# CPU.net
KiCad netlist of a schematic drawn in Altium Designer
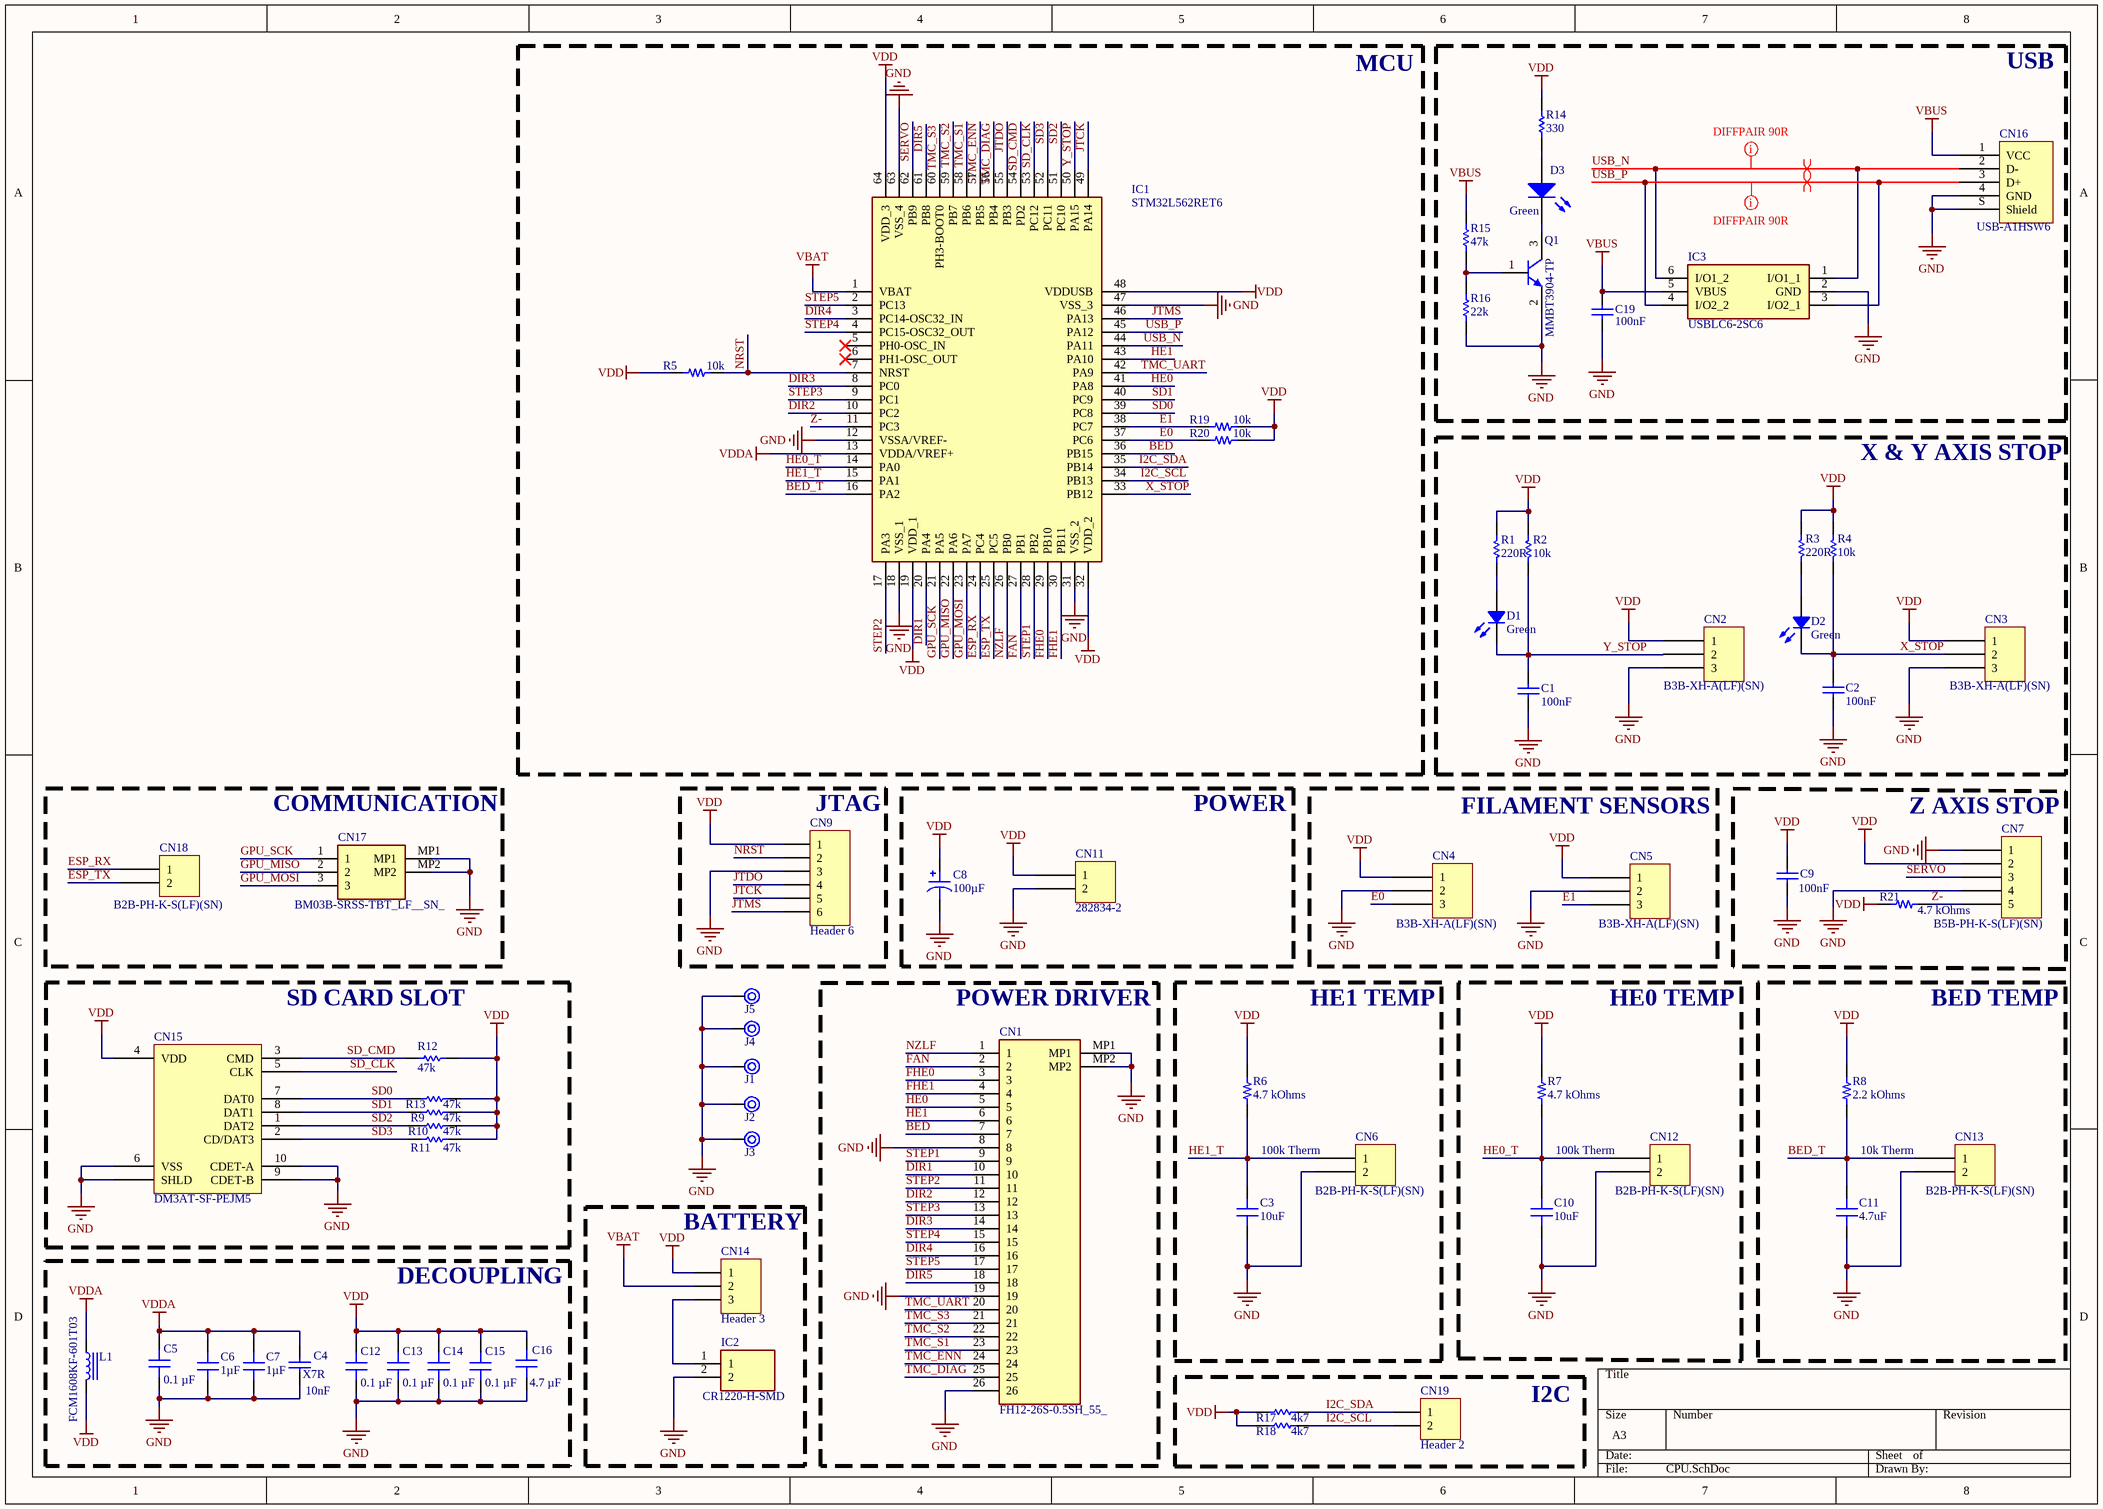
[diagram p0: CPU.SchDoc]

(export (version "E")
  (design (tool "Eeschema 10.0.6"))
  (components
    (comp (ref "C1")
      (value "100nF")
      (footprint "1608[0603]")
      (description "Capacitor")
      (fields (field (name "Comment") "X5R") (field (name "PUBLISHER") "Altium Limited"))
      (libsource (lib "Miscellaneous Devices") (part "Cap"))
    )
    (comp (ref "C2")
      (value "100nF")
      (footprint "1608[0603]")
      (description "Capacitor")
      (fields (field (name "Comment") "X5R") (field (name "PUBLISHER") "Altium Limited"))
      (libsource (lib "Miscellaneous Devices") (part "Cap"))
    )
    (comp (ref "C3")
      (value "10uF")
      (footprint "CAP 0603_1608")
      (description "CAP CER 1UF 16V X5R 0603")
      (fields (field (name "PART NUMBER") "0603YD105KAT4A") (field (name "MANUFACTURER") "AVX Corporation"))
      (libsource (lib "Celestial Altium Library - altium_library") (part "Capacitor"))
    )
    (comp (ref "C4")
      (value "X7R")
      (footprint "1608[0603]")
      (description "Capacitor")
      (fields (field (name "ALTIUM_VALUE") "10nF") (field (name "PUBLISHER") "Altium Limited"))
      (libsource (lib "Miscellaneous Devices") (part "Cap"))
    )
    (comp (ref "C5")
      (value "0.1 µF")
      (footprint "CAP 0603_1608")
      (description "CAP CER 0.1UF 100V X7R 0603")
      (fields
        (field (name "PART NUMBER") "0603B104K101CT")
        (field (name "MANUFACTURER") "Walsin Technology Corporation")
      )
      (libsource (lib "Celestial Altium Library - altium_library") (part "Capacitor"))
    )
    (comp (ref "C6")
      (value "1µF")
      (footprint "CAP 0603_1608")
      (description "CAP CER 1UF 16V X5R 0603")
      (fields (field (name "PART NUMBER") "0603YD105KAT4A") (field (name "MANUFACTURER") "AVX Corporation"))
      (libsource (lib "Celestial Altium Library - altium_library") (part "Capacitor"))
    )
    (comp (ref "C7")
      (value "1µF")
      (footprint "CAP 0603_1608")
      (description "CAP CER 1UF 16V X5R 0603")
      (fields (field (name "PART NUMBER") "0603YD105KAT4A") (field (name "MANUFACTURER") "AVX Corporation"))
      (libsource (lib "Celestial Altium Library - altium_library") (part "Capacitor"))
    )
    (comp (ref "C8")
      (value "100µF")
      (footprint "CAP ALSMD POLY 5.3MM H6.0MM")
      (description "CAP ALUM POLY 100UF 20% 6.3V SMD")
      (fields
        (field (name "PART NUMBER") "6SVPC100M")
        (field (name "MANUFACTURER") "Panasonic Electronic Components")
      )
      (libsource (lib "Celestial Altium Library - altium_library") (part "Polarised Capacitor"))
    )
    (comp (ref "C9")
      (value "100nF")
      (footprint "1608[0603]")
      (description "Capacitor")
      (fields (field (name "Comment") "X5R") (field (name "PUBLISHER") "Altium Limited"))
      (libsource (lib "Miscellaneous Devices") (part "Cap"))
    )
    (comp (ref "C10")
      (value "10uF")
      (footprint "CAP 0603_1608")
      (description "CAP CER 1UF 16V X5R 0603")
      (fields (field (name "PART NUMBER") "0603YD105KAT4A") (field (name "MANUFACTURER") "AVX Corporation"))
      (libsource (lib "Celestial Altium Library - altium_library") (part "Capacitor"))
    )
    (comp (ref "C11")
      (value "4.7uF")
      (footprint "CAP 0603_1608")
      (description "CAP CER 1UF 16V X5R 0603")
      (fields (field (name "PART NUMBER") "0603YD105KAT4A") (field (name "MANUFACTURER") "AVX Corporation"))
      (libsource (lib "Celestial Altium Library - altium_library") (part "Capacitor"))
    )
    (comp (ref "C12")
      (value "0.1 µF")
      (footprint "CAP 0603_1608")
      (description "CAP CER 0.1UF 100V X7R 0603")
      (fields
        (field (name "PART NUMBER") "0603B104K101CT")
        (field (name "MANUFACTURER") "Walsin Technology Corporation")
      )
      (libsource (lib "Celestial Altium Library - altium_library") (part "Capacitor"))
    )
    (comp (ref "C13")
      (value "0.1 µF")
      (footprint "CAP 0603_1608")
      (description "CAP CER 0.1UF 100V X7R 0603")
      (fields
        (field (name "PART NUMBER") "0603B104K101CT")
        (field (name "MANUFACTURER") "Walsin Technology Corporation")
      )
      (libsource (lib "Celestial Altium Library - altium_library") (part "Capacitor"))
    )
    (comp (ref "C14")
      (value "0.1 µF")
      (footprint "CAP 0603_1608")
      (description "CAP CER 0.1UF 100V X7R 0603")
      (fields
        (field (name "PART NUMBER") "0603B104K101CT")
        (field (name "MANUFACTURER") "Walsin Technology Corporation")
      )
      (libsource (lib "Celestial Altium Library - altium_library") (part "Capacitor"))
    )
    (comp (ref "C15")
      (value "0.1 µF")
      (footprint "CAP 0603_1608")
      (description "CAP CER 0.1UF 100V X7R 0603")
      (fields
        (field (name "PART NUMBER") "0603B104K101CT")
        (field (name "MANUFACTURER") "Walsin Technology Corporation")
      )
      (libsource (lib "Celestial Altium Library - altium_library") (part "Capacitor"))
    )
    (comp (ref "C16")
      (value "4.7 µF")
      (footprint "CAP 0603_1608")
      (description "CAP CER 4.7UF 16V X5R 0603")
      (fields
        (field (name "PART NUMBER") "GRM185R61C475KE11D")
        (field (name "MANUFACTURER") "Murata Electronics")
      )
      (libsource (lib "Celestial Altium Library - altium_library") (part "Capacitor"))
    )
    (comp (ref "C19")
      (value "100nF")
      (footprint "1608[0603]")
      (description "Capacitor")
      (fields (field (name "Comment") "Cap") (field (name "PUBLISHER") "Altium Limited"))
      (libsource (lib "Miscellaneous Devices") (part "Cap"))
    )
    (comp (ref "CN1")
      (value "FH12-26S-0.5SH_55_")
      (footprint "SamacSys:FH1226S05SH55")
      (description "Connector")
      (fields
        (field (name "MANUFACTURER_PART_NUMBER") "FH12-26S-0.5SH(55)")
        (field (name "MOUSER PART NUMBER") "798-FH12-26S-0.5SH55")
      )
      (libsource (lib "SamacSys") (part "FH12-26S-0.5SH_55_"))
    )
    (comp (ref "CN2")
      (value "B3B-XH-A(LF)(SN)")
      (footprint "JST XH B3B-XH-A")
      (description "CONN HEADER VERT 3POS 2.5MM")
      (fields (field (name "MANUFACTURER") "JST Sales America Inc."))
      (libsource (lib "Celestial Altium Library - altium_library") (part "3 Pin"))
    )
    (comp (ref "CN3")
      (value "B3B-XH-A(LF)(SN)")
      (footprint "JST XH B3B-XH-A")
      (description "CONN HEADER VERT 3POS 2.5MM")
      (fields (field (name "MANUFACTURER") "JST Sales America Inc."))
      (libsource (lib "Celestial Altium Library - altium_library") (part "3 Pin"))
    )
    (comp (ref "CN4")
      (value "B3B-XH-A(LF)(SN)")
      (footprint "JST XH B3B-XH-A")
      (description "CONN HEADER VERT 3POS 2.5MM")
      (fields (field (name "MANUFACTURER") "JST Sales America Inc."))
      (libsource (lib "Celestial Altium Library - altium_library") (part "3 Pin"))
    )
    (comp (ref "CN5")
      (value "B3B-XH-A(LF)(SN)")
      (footprint "JST XH B3B-XH-A")
      (description "CONN HEADER VERT 3POS 2.5MM")
      (fields (field (name "MANUFACTURER") "JST Sales America Inc."))
      (libsource (lib "Celestial Altium Library - altium_library") (part "3 Pin"))
    )
    (comp (ref "CN6")
      (value "B2B-PH-K-S(LF)(SN)")
      (footprint "JST B2B-PH-K")
      (description "CONN HEADER VERT 2POS 2MM")
      (fields (field (name "MANUFACTURER") "JST Sales America Inc."))
      (libsource (lib "Celestial Altium Library - altium_library") (part "2 Pin"))
    )
    (comp (ref "CN7")
      (value "B5B-PH-K-S(LF)(SN)")
      (footprint "JST B5B-PH-K")
      (description "CONN HEADER VERT 5POS 2MM")
      (fields (field (name "MANUFACTURER") "JST Sales America Inc."))
      (libsource (lib "Celestial Altium Library - altium_library") (part "5 Pin"))
    )
    (comp (ref "CN9")
      (value "Header 6")
      (footprint "HDR1X6")
      (description "Header, 6-Pin")
      (fields (field (name "PUBLISHER") "Altium Limited"))
      (libsource (lib "Miscellaneous Connectors") (part "Header 6"))
    )
    (comp (ref "CN11")
      (value "282834-2")
      (footprint "TE 282834-2")
      (description "TERM BLK 2P SIDE ENT 2.54MM PCB")
      (fields (field (name "MANUFACTURER") "TE Connectivity AMP Connectors") (field (name "VOLTAGE") "150V"))
      (libsource (lib "Celestial Altium Library - altium_library") (part "2 Pin"))
    )
    (comp (ref "CN12")
      (value "B2B-PH-K-S(LF)(SN)")
      (footprint "JST B2B-PH-K")
      (description "CONN HEADER VERT 2POS 2MM")
      (fields (field (name "MANUFACTURER") "JST Sales America Inc."))
      (libsource (lib "Celestial Altium Library - altium_library") (part "2 Pin"))
    )
    (comp (ref "CN13")
      (value "B2B-PH-K-S(LF)(SN)")
      (footprint "JST B2B-PH-K")
      (description "CONN HEADER VERT 2POS 2MM")
      (fields (field (name "MANUFACTURER") "JST Sales America Inc."))
      (libsource (lib "Celestial Altium Library - altium_library") (part "2 Pin"))
    )
    (comp (ref "CN14")
      (value "Header 3")
      (footprint "HDR1X3")
      (description "Header, 3-Pin")
      (fields (field (name "PUBLISHER") "Altium Limited"))
      (libsource (lib "Miscellaneous Connectors") (part "Header 3"))
    )
    (comp (ref "CN15")
      (value "DM3AT-SF-PEJM5")
      (footprint "HIROSE DM3AT-SF-PEJM5")
      (description "CONN MICRO SD CARD PUSH-PUSH R/A")
      (fields (field (name "MANUFACTURER") "Hirose Electric Co Ltd"))
      (libsource (lib "Celestial Altium Library - altium_library") (part "Hirose DM3 MicroSD"))
    )
    (comp (ref "CN16")
      (value "USB-A1HSW6")
      (footprint "ON SHORE TECHNOLOGY USB-A1HSW6")
      (description "CONN RCPT TYPEA 4POS R/A")
      (fields (field (name "MANUFACTURER") "On Shore Technology Inc."))
      (libsource (lib "Celestial Altium Library - altium_library") (part "USB 2.0 TYPE A"))
    )
    (comp (ref "CN17")
      (value "BM03B-SRSS-TBT_LF__SN_")
      (footprint "SamacSys:BM03BSRSSTBTLFSN")
      (description "Connector")
      (fields (field (name "MANUFACTURER_PART_NUMBER") "BM03B-SRSS-TBT(LF)(SN)"))
      (libsource (lib "*") (part "BM03B-SRSS-TBT_LF__SN_"))
    )
    (comp (ref "CN18")
      (value "B2B-PH-K-S(LF)(SN)")
      (footprint "JST B2B-PH-K")
      (description "CONN HEADER VERT 2POS 2MM")
      (fields (field (name "MANUFACTURER") "JST Sales America Inc."))
      (libsource (lib "Celestial Altium Library - altium_library") (part "2 Pin"))
    )
    (comp (ref "CN19")
      (value "Header 2")
      (footprint "HDR1X2")
      (description "Header, 2-Pin")
      (fields (field (name "PUBLISHER") "Altium Limited"))
      (libsource (lib "Miscellaneous Connectors") (part "Header 2"))
    )
    (comp (ref "D1")
      (value "Green")
      (footprint "LED 0805_2012 GREEN")
      (description "LED GREEN CLEAR 0805 SMD")
      (fields
        (field (name "PART NUMBER") "QTLP630C4TR")
        (field (name "MANUFACTURER") "Everlight Electronics Co Ltd")
      )
      (libsource (lib "Celestial Altium Library - altium_library") (part "LED"))
    )
    (comp (ref "D2")
      (value "Green")
      (footprint "LED 0805_2012 GREEN")
      (description "LED GREEN CLEAR 0805 SMD")
      (fields
        (field (name "PART NUMBER") "QTLP630C4TR")
        (field (name "MANUFACTURER") "Everlight Electronics Co Ltd")
      )
      (libsource (lib "Celestial Altium Library - altium_library") (part "LED"))
    )
    (comp (ref "D3")
      (value "Green")
      (footprint "1608[0603]")
      (description "Typical BLUE SiC LED")
      (fields (field (name "PUBLISHER") "Altium Limited"))
      (libsource (lib "Miscellaneous Devices") (part "LED3"))
    )
    (comp (ref "IC1")
      (value "STM32L562RET6")
      (footprint "SamacSys:QFP50P1200X1200X160-64N")
      (description "Integrated Circuit")
      (fields (field (name "MOUSER PART NUMBER") "511-STM32L562RET6"))
      (libsource (lib "*") (part "STM32L562RET6"))
    )
    (comp (ref "IC2")
      (value "CR1220-H-SMD")
      (footprint "SamacSys:CR1220HSMD")
      (description "Integrated Circuit")
      (libsource (lib "*") (part "CR1220-H-SMD"))
    )
    (comp (ref "IC3")
      (value "USBLC6-2SC6")
      (footprint "SamacSys:SOT95P280X145-6N")
      (description "Integrated Circuit")
      (fields (field (name "MOUSER PART NUMBER") "511-USBLC6-2SC6"))
      (libsource (lib "*") (part "USBLC6-2SC6"))
    )
    (comp (ref "J1")
      (value "PTH 3.2mm")
      (footprint "PTH 3.2mm")
      (libsource (lib "Integrated_Library1") (part "PTH 3.2mm"))
    )
    (comp (ref "J2")
      (value "PTH 3.2mm")
      (footprint "PTH 3.2mm")
      (libsource (lib "Integrated_Library1") (part "PTH 3.2mm"))
    )
    (comp (ref "J3")
      (value "PTH 3.2mm")
      (footprint "PTH 3.2mm")
      (libsource (lib "Integrated_Library1") (part "PTH 3.2mm"))
    )
    (comp (ref "J4")
      (value "PTH 3.2mm")
      (footprint "PTH 3.2mm")
      (libsource (lib "Integrated_Library1") (part "PTH 3.2mm"))
    )
    (comp (ref "J5")
      (value "PTH 3.2mm")
      (footprint "PTH 3.2mm")
      (libsource (lib "Integrated_Library1") (part "PTH 3.2mm"))
    )
    (comp (ref "L1")
      (value "FCM1608KF-601T03")
      (footprint "IND 0603_1608 RF WW")
      (description "FIXED IND 27NH 780MA 200 MOHM")
      (fields (field (name "PART NUMBER") "744917127") (field (name "MANUFACTURER") "Würth Elektronik"))
      (libsource (lib "Celestial Altium Library - altium_library") (part "Inductor"))
    )
    (comp (ref "Q1")
      (value "MMBT3904-TP")
      (footprint "MCCSEMI SOT-23-3")
      (description "TRANS NPN 40V 0.2A SOT23")
      (fields (field (name "MANUFACTURER") "Micro Commercial Co"))
      (libsource (lib "Celestial Altium Library - altium_library") (part "MCCSEMI NPN SOT-23-3"))
    )
    (comp (ref "R1")
      (value "220R")
      (footprint "1608[0603]")
      (description "Resistor")
      (fields (field (name "Comment") "Res1") (field (name "PUBLISHER") "Altium Limited"))
      (libsource (lib "Miscellaneous Devices") (part "Res1"))
    )
    (comp (ref "R2")
      (value "10k")
      (footprint "1608[0603]")
      (description "Resistor")
      (fields (field (name "Comment") "Res1") (field (name "PUBLISHER") "Altium Limited"))
      (libsource (lib "Miscellaneous Devices") (part "Res1"))
    )
    (comp (ref "R3")
      (value "220R")
      (footprint "1608[0603]")
      (description "Resistor")
      (fields (field (name "Comment") "Res1") (field (name "PUBLISHER") "Altium Limited"))
      (libsource (lib "Miscellaneous Devices") (part "Res1"))
    )
    (comp (ref "R4")
      (value "10k")
      (footprint "1608[0603]")
      (description "Resistor")
      (fields (field (name "Comment") "Res1") (field (name "PUBLISHER") "Altium Limited"))
      (libsource (lib "Miscellaneous Devices") (part "Res1"))
    )
    (comp (ref "R5")
      (value "10k")
      (footprint "RES 0603_1608")
      (description "RES 10K OHM 1% 1/5W 0603")
      (fields (field (name "PART NUMBER") "RC0603FR-7W10KL") (field (name "MANUFACTURER") "Yageo"))
      (libsource (lib "Celestial Altium Library - altium_library") (part "Resistor"))
    )
    (comp (ref "R6")
      (value "4.7 kOhms")
      (footprint "RES 0603_1608")
      (description "RES 4.7K OHM 0.1% 1/5W 0603")
      (fields
        (field (name "PART NUMBER") "RS73G1JTTD4701B")
        (field (name "MANUFACTURER") "KOA Speer Electronics, Inc.")
      )
      (libsource (lib "Celestial Altium Library - altium_library") (part "Resistor"))
    )
    (comp (ref "R7")
      (value "4.7 kOhms")
      (footprint "RES 0603_1608")
      (description "RES 4.7K OHM 0.1% 1/5W 0603")
      (fields
        (field (name "PART NUMBER") "RS73G1JTTD4701B")
        (field (name "MANUFACTURER") "KOA Speer Electronics, Inc.")
      )
      (libsource (lib "Celestial Altium Library - altium_library") (part "Resistor"))
    )
    (comp (ref "R8")
      (value "2.2 kOhms")
      (footprint "RES 0603_1608")
      (description "RES 2.2K OHM 0.1% 1/5W 0603")
      (fields
        (field (name "PART NUMBER") "RS73G1JTTD2201B")
        (field (name "MANUFACTURER") "KOA Speer Electronics, Inc.")
      )
      (libsource (lib "Celestial Altium Library - altium_library") (part "Resistor"))
    )
    (comp (ref "R9")
      (value "47k")
      (footprint "1608[0603]")
      (description "Resistor")
      (fields (field (name "Comment") "Res1") (field (name "PUBLISHER") "Altium Limited"))
      (libsource (lib "Miscellaneous Devices") (part "Res1"))
    )
    (comp (ref "R10")
      (value "47k")
      (footprint "1608[0603]")
      (description "Resistor")
      (fields (field (name "Comment") "Res1") (field (name "PUBLISHER") "Altium Limited"))
      (libsource (lib "Miscellaneous Devices") (part "Res1"))
    )
    (comp (ref "R11")
      (value "47k")
      (footprint "1608[0603]")
      (description "Resistor")
      (fields (field (name "Comment") "Res1") (field (name "PUBLISHER") "Altium Limited"))
      (libsource (lib "Miscellaneous Devices") (part "Res1"))
    )
    (comp (ref "R12")
      (value "47k")
      (footprint "1608[0603]")
      (description "Resistor")
      (fields (field (name "Comment") "Res1") (field (name "PUBLISHER") "Altium Limited"))
      (libsource (lib "Miscellaneous Devices") (part "Res1"))
    )
    (comp (ref "R13")
      (value "47k")
      (footprint "1608[0603]")
      (description "Resistor")
      (fields (field (name "Comment") "Res1") (field (name "PUBLISHER") "Altium Limited"))
      (libsource (lib "Miscellaneous Devices") (part "Res1"))
    )
    (comp (ref "R14")
      (value "330")
      (footprint "1608[0603]")
      (description "Resistor")
      (fields (field (name "Comment") "Res1") (field (name "PUBLISHER") "Altium Limited"))
      (libsource (lib "Miscellaneous Devices") (part "Res1"))
    )
    (comp (ref "R15")
      (value "47k")
      (footprint "1608[0603]")
      (description "Resistor")
      (fields (field (name "Comment") "Res1") (field (name "PUBLISHER") "Altium Limited"))
      (libsource (lib "Miscellaneous Devices") (part "Res1"))
    )
    (comp (ref "R16")
      (value "22k")
      (footprint "1608[0603]")
      (description "Resistor")
      (fields (field (name "Comment") "Res1") (field (name "PUBLISHER") "Altium Limited"))
      (libsource (lib "Miscellaneous Devices") (part "Res1"))
    )
    (comp (ref "R17")
      (value "4k7")
      (footprint "1608[0603]")
      (description "Resistor")
      (fields (field (name "Comment") "Res1") (field (name "PUBLISHER") "Altium Limited"))
      (libsource (lib "Miscellaneous Devices") (part "Res1"))
    )
    (comp (ref "R18")
      (value "4k7")
      (footprint "1608[0603]")
      (description "Resistor")
      (fields (field (name "Comment") "Res1") (field (name "PUBLISHER") "Altium Limited"))
      (libsource (lib "Miscellaneous Devices") (part "Res1"))
    )
    (comp (ref "R19")
      (value "10k")
      (footprint "RES 0603_1608")
      (description "RES 10K OHM 1% 1/5W 0603")
      (fields (field (name "PART NUMBER") "RC0603FR-7W10KL") (field (name "MANUFACTURER") "Yageo"))
      (libsource (lib "Celestial Altium Library - altium_library") (part "Resistor"))
    )
    (comp (ref "R20")
      (value "10k")
      (footprint "RES 0603_1608")
      (description "RES 10K OHM 1% 1/5W 0603")
      (fields (field (name "PART NUMBER") "RC0603FR-7W10KL") (field (name "MANUFACTURER") "Yageo"))
      (libsource (lib "Celestial Altium Library - altium_library") (part "Resistor"))
    )
    (comp (ref "R21")
      (value "4.7 kOhms")
      (footprint "RES 0603_1608")
      (description "RES 4.7K OHM 0.1% 1/5W 0603")
      (fields
        (field (name "PART NUMBER") "RS73G1JTTD4701B")
        (field (name "MANUFACTURER") "KOA Speer Electronics, Inc.")
      )
      (libsource (lib "Celestial Altium Library - altium_library") (part "Resistor"))
    )
  )
  (nets
    (net (code "1") (name "/BED") (class "Default")
      (node (ref "CN1") (pin "7") (pinfunction "7_7") (pintype "passive"))
      (node (ref "IC1") (pin "36") (pinfunction "PB15_36") (pintype "passive"))
    )
    (net (code "2") (name "/BED_T") (class "Default")
      (node (ref "C11") (pin "2") (pinfunction "2_2") (pintype "passive"))
      (node (ref "CN13") (pin "1") (pinfunction "1_1") (pintype "passive"))
      (node (ref "IC1") (pin "16") (pinfunction "PA2_16") (pintype "passive"))
      (node (ref "R8") (pin "1") (pinfunction "1_1") (pintype "passive"))
    )
    (net (code "3") (name "/DIR1") (class "Default")
      (node (ref "CN1") (pin "10") (pinfunction "10_10") (pintype "passive"))
      (node (ref "IC1") (pin "20") (pinfunction "PA4_20") (pintype "passive"))
    )
    (net (code "4") (name "/DIR2") (class "Default")
      (node (ref "CN1") (pin "12") (pinfunction "12_12") (pintype "passive"))
      (node (ref "IC1") (pin "10") (pinfunction "PC2_10") (pintype "passive"))
    )
    (net (code "5") (name "/DIR3") (class "Default")
      (node (ref "CN1") (pin "14") (pinfunction "14_14") (pintype "passive"))
      (node (ref "IC1") (pin "8") (pinfunction "PC0_8") (pintype "passive"))
    )
    (net (code "6") (name "/DIR4") (class "Default")
      (node (ref "CN1") (pin "16") (pinfunction "16_16") (pintype "passive"))
      (node (ref "IC1") (pin "3") (pinfunction "PC14-OSC32_IN_3") (pintype "passive"))
    )
    (net (code "7") (name "/DIR5") (class "Default")
      (node (ref "CN1") (pin "18") (pinfunction "18_18") (pintype "passive"))
      (node (ref "IC1") (pin "61") (pinfunction "PB8_61") (pintype "passive"))
    )
    (net (code "8") (name "/E0") (class "Default")
      (node (ref "CN4") (pin "3") (pinfunction "3_3") (pintype "passive"))
      (node (ref "IC1") (pin "37") (pinfunction "PC6_37") (pintype "passive"))
      (node (ref "R20") (pin "1") (pinfunction "1_1") (pintype "passive"))
    )
    (net (code "9") (name "/E1") (class "Default")
      (node (ref "CN5") (pin "3") (pinfunction "3_3") (pintype "passive"))
      (node (ref "IC1") (pin "38") (pinfunction "PC7_38") (pintype "passive"))
      (node (ref "R19") (pin "1") (pinfunction "1_1") (pintype "passive"))
    )
    (net (code "10") (name "/ESP_RX") (class "Default")
      (node (ref "CN18") (pin "1") (pinfunction "1_1") (pintype "passive"))
      (node (ref "IC1") (pin "24") (pinfunction "PC4_24") (pintype "passive"))
    )
    (net (code "11") (name "/ESP_TX") (class "Default")
      (node (ref "CN18") (pin "2") (pinfunction "2_2") (pintype "passive"))
      (node (ref "IC1") (pin "25") (pinfunction "PC5_25") (pintype "passive"))
    )
    (net (code "12") (name "/FAN") (class "Default")
      (node (ref "CN1") (pin "2") (pinfunction "2_2") (pintype "passive"))
      (node (ref "IC1") (pin "27") (pinfunction "PB1_27") (pintype "passive"))
    )
    (net (code "13") (name "/FHE0") (class "Default")
      (node (ref "CN1") (pin "3") (pinfunction "3_3") (pintype "passive"))
      (node (ref "IC1") (pin "29") (pinfunction "PB10_29") (pintype "passive"))
    )
    (net (code "14") (name "/FHE1") (class "Default")
      (node (ref "CN1") (pin "4") (pinfunction "4_4") (pintype "passive"))
      (node (ref "IC1") (pin "30") (pinfunction "PB11_30") (pintype "passive"))
    )
    (net (code "15") (name "/GPU_MISO") (class "Default")
      (node (ref "CN17") (pin "2") (pinfunction "2_2") (pintype "passive"))
      (node (ref "IC1") (pin "22") (pinfunction "PA6_22") (pintype "passive"))
    )
    (net (code "16") (name "/GPU_MOSI") (class "Default")
      (node (ref "CN17") (pin "3") (pinfunction "3_3") (pintype "passive"))
      (node (ref "IC1") (pin "23") (pinfunction "PA7_23") (pintype "passive"))
    )
    (net (code "17") (name "/GPU_SCK") (class "Default")
      (node (ref "CN17") (pin "1") (pinfunction "1_1") (pintype "passive"))
      (node (ref "IC1") (pin "21") (pinfunction "PA5_21") (pintype "passive"))
    )
    (net (code "18") (name "/HE0") (class "Default")
      (node (ref "CN1") (pin "5") (pinfunction "5_5") (pintype "passive"))
      (node (ref "IC1") (pin "41") (pinfunction "PA8_41") (pintype "passive"))
    )
    (net (code "19") (name "/HE0_T") (class "Default")
      (node (ref "C10") (pin "2") (pinfunction "2_2") (pintype "passive"))
      (node (ref "CN12") (pin "1") (pinfunction "1_1") (pintype "passive"))
      (node (ref "IC1") (pin "14") (pinfunction "PA0_14") (pintype "passive"))
      (node (ref "R7") (pin "1") (pinfunction "1_1") (pintype "passive"))
    )
    (net (code "20") (name "/HE1") (class "Default")
      (node (ref "CN1") (pin "6") (pinfunction "6_6") (pintype "passive"))
      (node (ref "IC1") (pin "43") (pinfunction "PA10_43") (pintype "passive"))
    )
    (net (code "21") (name "/HE1_T") (class "Default")
      (node (ref "C3") (pin "2") (pinfunction "2_2") (pintype "passive"))
      (node (ref "CN6") (pin "1") (pinfunction "1_1") (pintype "passive"))
      (node (ref "IC1") (pin "15") (pinfunction "PA1_15") (pintype "passive"))
      (node (ref "R6") (pin "1") (pinfunction "1_1") (pintype "passive"))
    )
    (net (code "22") (name "/I2C_SCL") (class "Default")
      (node (ref "CN19") (pin "2") (pinfunction "2_2") (pintype "passive"))
      (node (ref "IC1") (pin "34") (pinfunction "PB13_34") (pintype "passive"))
      (node (ref "R18") (pin "2") (pinfunction "2_2") (pintype "passive"))
    )
    (net (code "23") (name "/I2C_SDA") (class "Default")
      (node (ref "CN19") (pin "1") (pinfunction "1_1") (pintype "passive"))
      (node (ref "IC1") (pin "35") (pinfunction "PB14_35") (pintype "passive"))
      (node (ref "R17") (pin "2") (pinfunction "2_2") (pintype "passive"))
    )
    (net (code "24") (name "/JTCK") (class "Default")
      (node (ref "CN9") (pin "5") (pinfunction "5_5") (pintype "passive"))
      (node (ref "IC1") (pin "49") (pinfunction "PA14_49") (pintype "passive"))
    )
    (net (code "25") (name "/JTDO") (class "Default")
      (node (ref "CN9") (pin "4") (pinfunction "4_4") (pintype "passive"))
      (node (ref "IC1") (pin "55") (pinfunction "PB3_55") (pintype "passive"))
    )
    (net (code "26") (name "/JTMS") (class "Default")
      (node (ref "CN9") (pin "6") (pinfunction "6_6") (pintype "passive"))
      (node (ref "IC1") (pin "46") (pinfunction "PA13_46") (pintype "passive"))
    )
    (net (code "27") (name "/NRST") (class "Default")
      (node (ref "CN9") (pin "2") (pinfunction "2_2") (pintype "passive"))
      (node (ref "IC1") (pin "7") (pinfunction "NRST_7") (pintype "passive"))
      (node (ref "R5") (pin "2") (pinfunction "2_2") (pintype "passive"))
    )
    (net (code "28") (name "/NZLF") (class "Default")
      (node (ref "CN1") (pin "1") (pinfunction "1_1") (pintype "passive"))
      (node (ref "IC1") (pin "26") (pinfunction "PB0_26") (pintype "passive"))
    )
    (net (code "29") (name "/SD0") (class "Default")
      (node (ref "CN15") (pin "7") (pinfunction "DAT0_7") (pintype "passive"))
      (node (ref "IC1") (pin "39") (pinfunction "PC8_39") (pintype "passive"))
      (node (ref "R13") (pin "1") (pinfunction "1_1") (pintype "passive"))
    )
    (net (code "30") (name "/SD1") (class "Default")
      (node (ref "CN15") (pin "8") (pinfunction "DAT1_8") (pintype "passive"))
      (node (ref "IC1") (pin "40") (pinfunction "PC9_40") (pintype "passive"))
      (node (ref "R9") (pin "2") (pinfunction "2_2") (pintype "passive"))
    )
    (net (code "31") (name "/SD2") (class "Default")
      (node (ref "CN15") (pin "1") (pinfunction "DAT2_1") (pintype "passive"))
      (node (ref "IC1") (pin "51") (pinfunction "PC10_51") (pintype "passive"))
      (node (ref "R10") (pin "1") (pinfunction "1_1") (pintype "passive"))
    )
    (net (code "32") (name "/SD3") (class "Default")
      (node (ref "CN15") (pin "2") (pinfunction "CD/DAT3_2") (pintype "passive"))
      (node (ref "IC1") (pin "52") (pinfunction "PC11_52") (pintype "passive"))
      (node (ref "R11") (pin "1") (pinfunction "1_1") (pintype "passive"))
    )
    (net (code "33") (name "/SD_CLK") (class "Default")
      (node (ref "CN15") (pin "5") (pinfunction "CLK_5") (pintype "passive"))
      (node (ref "IC1") (pin "53") (pinfunction "PC12_53") (pintype "passive"))
    )
    (net (code "34") (name "/SD_CMD") (class "Default")
      (node (ref "CN15") (pin "3") (pinfunction "CMD_3") (pintype "passive"))
      (node (ref "IC1") (pin "54") (pinfunction "PD2_54") (pintype "passive"))
      (node (ref "R12") (pin "2") (pinfunction "2_2") (pintype "passive"))
    )
    (net (code "35") (name "/SERVO") (class "Default")
      (node (ref "CN7") (pin "3") (pinfunction "3_3") (pintype "passive"))
      (node (ref "IC1") (pin "62") (pinfunction "PB9_62") (pintype "passive"))
    )
    (net (code "36") (name "/STEP1") (class "Default")
      (node (ref "CN1") (pin "9") (pinfunction "9_9") (pintype "passive"))
      (node (ref "IC1") (pin "28") (pinfunction "PB2_28") (pintype "passive"))
    )
    (net (code "37") (name "/STEP2") (class "Default")
      (node (ref "CN1") (pin "11") (pinfunction "11_11") (pintype "passive"))
      (node (ref "IC1") (pin "17") (pinfunction "PA3_17") (pintype "passive"))
    )
    (net (code "38") (name "/STEP3") (class "Default")
      (node (ref "CN1") (pin "13") (pinfunction "13_13") (pintype "passive"))
      (node (ref "IC1") (pin "9") (pinfunction "PC1_9") (pintype "passive"))
    )
    (net (code "39") (name "/STEP4") (class "Default")
      (node (ref "CN1") (pin "15") (pinfunction "15_15") (pintype "passive"))
      (node (ref "IC1") (pin "4") (pinfunction "PC15-OSC32_OUT_4") (pintype "passive"))
    )
    (net (code "40") (name "/STEP5") (class "Default")
      (node (ref "CN1") (pin "17") (pinfunction "17_17") (pintype "passive"))
      (node (ref "IC1") (pin "2") (pinfunction "PC13_2") (pintype "passive"))
    )
    (net (code "41") (name "/TMC_DIAG") (class "Default")
      (node (ref "CN1") (pin "25") (pinfunction "25_25") (pintype "passive"))
      (node (ref "IC1") (pin "56") (pinfunction "PB4_56") (pintype "passive"))
    )
    (net (code "42") (name "/TMC_ENN") (class "Default")
      (node (ref "CN1") (pin "24") (pinfunction "24_24") (pintype "passive"))
      (node (ref "IC1") (pin "57") (pinfunction "PB5_57") (pintype "passive"))
    )
    (net (code "43") (name "/TMC_S1") (class "Default")
      (node (ref "CN1") (pin "23") (pinfunction "23_23") (pintype "passive"))
      (node (ref "IC1") (pin "58") (pinfunction "PB6_58") (pintype "passive"))
    )
    (net (code "44") (name "/TMC_S2") (class "Default")
      (node (ref "CN1") (pin "22") (pinfunction "22_22") (pintype "passive"))
      (node (ref "IC1") (pin "59") (pinfunction "PB7_59") (pintype "passive"))
    )
    (net (code "45") (name "/TMC_S3") (class "Default")
      (node (ref "CN1") (pin "21") (pinfunction "21_21") (pintype "passive"))
      (node (ref "IC1") (pin "60") (pinfunction "PH3-BOOT0_60") (pintype "passive"))
    )
    (net (code "46") (name "/TMC_UART") (class "Default")
      (node (ref "CN1") (pin "20") (pinfunction "20_20") (pintype "passive"))
      (node (ref "IC1") (pin "42") (pinfunction "PA9_42") (pintype "passive"))
    )
    (net (code "47") (name "/USB_N") (class "Default")
      (node (ref "CN16") (pin "2") (pinfunction "D-_2") (pintype "passive"))
      (node (ref "IC1") (pin "44") (pinfunction "PA11_44") (pintype "passive"))
      (node (ref "IC3") (pin "1") (pinfunction "I/O1_1_1") (pintype "passive"))
      (node (ref "IC3") (pin "6") (pinfunction "I/O1_2_6") (pintype "passive"))
    )
    (net (code "48") (name "/USB_P") (class "Default")
      (node (ref "CN16") (pin "3") (pinfunction "D+_3") (pintype "passive"))
      (node (ref "IC1") (pin "45") (pinfunction "PA12_45") (pintype "passive"))
      (node (ref "IC3") (pin "3") (pinfunction "I/O2_1_3") (pintype "passive"))
      (node (ref "IC3") (pin "4") (pinfunction "I/O2_2_4") (pintype "passive"))
    )
    (net (code "49") (name "/X_STOP") (class "Default")
      (node (ref "C2") (pin "1") (pinfunction "1_1") (pintype "passive"))
      (node (ref "CN3") (pin "2") (pinfunction "2_2") (pintype "passive"))
      (node (ref "D2") (pin "2") (pinfunction "2_2") (pintype "passive"))
      (node (ref "IC1") (pin "33") (pinfunction "PB12_33") (pintype "passive"))
      (node (ref "R4") (pin "2") (pinfunction "2_2") (pintype "passive"))
    )
    (net (code "50") (name "/Y_STOP") (class "Default")
      (node (ref "C1") (pin "1") (pinfunction "1_1") (pintype "passive"))
      (node (ref "CN2") (pin "2") (pinfunction "2_2") (pintype "passive"))
      (node (ref "D1") (pin "2") (pinfunction "2_2") (pintype "passive"))
      (node (ref "IC1") (pin "50") (pinfunction "PA15_50") (pintype "passive"))
      (node (ref "R2") (pin "2") (pinfunction "2_2") (pintype "passive"))
    )
    (net (code "51") (name "/Z-") (class "Default")
      (node (ref "CN7") (pin "5") (pinfunction "5_5") (pintype "passive"))
      (node (ref "IC1") (pin "11") (pinfunction "PC3_11") (pintype "passive"))
      (node (ref "R21") (pin "1") (pinfunction "1_1") (pintype "passive"))
    )
    (net (code "52") (name "GND") (class "Default")
      (node (ref "C1") (pin "2") (pinfunction "2_2") (pintype "passive"))
      (node (ref "C10") (pin "1") (pinfunction "1_1") (pintype "passive"))
      (node (ref "C11") (pin "1") (pinfunction "1_1") (pintype "passive"))
      (node (ref "C12") (pin "1") (pinfunction "1_1") (pintype "passive"))
      (node (ref "C13") (pin "1") (pinfunction "1_1") (pintype "passive"))
      (node (ref "C14") (pin "1") (pinfunction "1_1") (pintype "passive"))
      (node (ref "C15") (pin "1") (pinfunction "1_1") (pintype "passive"))
      (node (ref "C16") (pin "1") (pinfunction "1_1") (pintype "passive"))
      (node (ref "C19") (pin "1") (pinfunction "1_1") (pintype "passive"))
      (node (ref "C2") (pin "2") (pinfunction "2_2") (pintype "passive"))
      (node (ref "C3") (pin "1") (pinfunction "1_1") (pintype "passive"))
      (node (ref "C4") (pin "1") (pinfunction "1_1") (pintype "passive"))
      (node (ref "C5") (pin "1") (pinfunction "1_1") (pintype "passive"))
      (node (ref "C6") (pin "1") (pinfunction "1_1") (pintype "passive"))
      (node (ref "C7") (pin "1") (pinfunction "1_1") (pintype "passive"))
      (node (ref "C8") (pin "2") (pinfunction "2_2") (pintype "passive"))
      (node (ref "C9") (pin "2") (pinfunction "2_2") (pintype "passive"))
      (node (ref "CN1") (pin "19") (pinfunction "19_19") (pintype "passive"))
      (node (ref "CN1") (pin "26") (pinfunction "26_26") (pintype "passive"))
      (node (ref "CN1") (pin "8") (pinfunction "8_8") (pintype "passive"))
      (node (ref "CN1") (pin "MP1") (pinfunction "MP1_MP1") (pintype "passive"))
      (node (ref "CN1") (pin "MP2") (pinfunction "MP2_MP2") (pintype "passive"))
      (node (ref "CN11") (pin "2") (pinfunction "2_2") (pintype "passive"))
      (node (ref "CN12") (pin "2") (pinfunction "2_2") (pintype "passive"))
      (node (ref "CN13") (pin "2") (pinfunction "2_2") (pintype "passive"))
      (node (ref "CN15") (pin "10") (pinfunction "CDET-A_10") (pintype "passive"))
      (node (ref "CN15") (pin "6") (pinfunction "VSS_6") (pintype "passive"))
      (node (ref "CN15") (pin "9") (pinfunction "CDET-B_9") (pintype "passive"))
      (node (ref "CN15") (pin "S") (pinfunction "SHLD_S") (pintype "passive"))
      (node (ref "CN16") (pin "4") (pinfunction "GND_4") (pintype "passive"))
      (node (ref "CN16") (pin "S") (pinfunction "Shield_S") (pintype "passive"))
      (node (ref "CN17") (pin "MP1") (pinfunction "MP1_MP1") (pintype "passive"))
      (node (ref "CN17") (pin "MP2") (pinfunction "MP2_MP2") (pintype "passive"))
      (node (ref "CN2") (pin "3") (pinfunction "3_3") (pintype "passive"))
      (node (ref "CN3") (pin "3") (pinfunction "3_3") (pintype "passive"))
      (node (ref "CN4") (pin "2") (pinfunction "2_2") (pintype "passive"))
      (node (ref "CN5") (pin "2") (pinfunction "2_2") (pintype "passive"))
      (node (ref "CN6") (pin "2") (pinfunction "2_2") (pintype "passive"))
      (node (ref "CN7") (pin "1") (pinfunction "1_1") (pintype "passive"))
      (node (ref "CN7") (pin "4") (pinfunction "4_4") (pintype "passive"))
      (node (ref "CN9") (pin "3") (pinfunction "3_3") (pintype "passive"))
      (node (ref "IC1") (pin "12") (pinfunction "VSSA/VREF-_12") (pintype "passive"))
      (node (ref "IC1") (pin "18") (pinfunction "VSS_1_18") (pintype "passive"))
      (node (ref "IC1") (pin "31") (pinfunction "VSS_2_31") (pintype "passive"))
      (node (ref "IC1") (pin "47") (pinfunction "VSS_3_47") (pintype "passive"))
      (node (ref "IC1") (pin "63") (pinfunction "VSS_4_63") (pintype "passive"))
      (node (ref "IC2") (pin "2") (pinfunction "2_2") (pintype "passive"))
      (node (ref "IC3") (pin "2") (pinfunction "GND_2") (pintype "passive"))
      (node (ref "J1") (pin "0") (pinfunction "0_0") (pintype "passive"))
      (node (ref "J2") (pin "0") (pinfunction "0_0") (pintype "passive"))
      (node (ref "J3") (pin "0") (pinfunction "0_0") (pintype "passive"))
      (node (ref "J4") (pin "0") (pinfunction "0_0") (pintype "passive"))
      (node (ref "J5") (pin "0") (pinfunction "0_0") (pintype "passive"))
      (node (ref "Q1") (pin "2") (pinfunction "E_2") (pintype "passive"))
      (node (ref "R16") (pin "1") (pinfunction "1_1") (pintype "passive"))
    )
    (net (code "53") (name "Net-(CN14-Pad3)") (class "Default")
      (node (ref "CN14") (pin "3") (pinfunction "3_3") (pintype "passive"))
      (node (ref "IC2") (pin "1") (pinfunction "1_1") (pintype "passive"))
    )
    (net (code "54") (name "Net-(D1-Pad1)") (class "Default")
      (node (ref "D1") (pin "1") (pinfunction "1_1") (pintype "passive"))
      (node (ref "R1") (pin "2") (pinfunction "2_2") (pintype "passive"))
    )
    (net (code "55") (name "Net-(D2-Pad1)") (class "Default")
      (node (ref "D2") (pin "1") (pinfunction "1_1") (pintype "passive"))
      (node (ref "R3") (pin "2") (pinfunction "2_2") (pintype "passive"))
    )
    (net (code "56") (name "Net-(D3-A)") (class "Default")
      (node (ref "D3") (pin "1") (pinfunction "A_1") (pintype "passive"))
      (node (ref "R14") (pin "1") (pinfunction "1_1") (pintype "passive"))
    )
    (net (code "57") (name "Net-(D3-K)") (class "Default")
      (node (ref "D3") (pin "2") (pinfunction "K_2") (pintype "passive"))
      (node (ref "Q1") (pin "3") (pinfunction "C_3") (pintype "passive"))
    )
    (net (code "58") (name "Net-(Q1-B)") (class "Default")
      (node (ref "Q1") (pin "1") (pinfunction "B_1") (pintype "passive"))
      (node (ref "R15") (pin "1") (pinfunction "1_1") (pintype "passive"))
      (node (ref "R16") (pin "2") (pinfunction "2_2") (pintype "passive"))
    )
    (net (code "59") (name "VBAT") (class "Default")
      (node (ref "CN14") (pin "2") (pinfunction "2_2") (pintype "passive"))
      (node (ref "IC1") (pin "1") (pinfunction "VBAT_1") (pintype "passive"))
    )
    (net (code "60") (name "VBUS") (class "Default")
      (node (ref "C19") (pin "2") (pinfunction "2_2") (pintype "passive"))
      (node (ref "CN16") (pin "1") (pinfunction "VCC_1") (pintype "passive"))
      (node (ref "IC3") (pin "5") (pinfunction "VBUS_5") (pintype "passive"))
      (node (ref "R15") (pin "2") (pinfunction "2_2") (pintype "passive"))
    )
    (net (code "61") (name "VDD") (class "Default")
      (node (ref "C12") (pin "2") (pinfunction "2_2") (pintype "passive"))
      (node (ref "C13") (pin "2") (pinfunction "2_2") (pintype "passive"))
      (node (ref "C14") (pin "2") (pinfunction "2_2") (pintype "passive"))
      (node (ref "C15") (pin "2") (pinfunction "2_2") (pintype "passive"))
      (node (ref "C16") (pin "2") (pinfunction "2_2") (pintype "passive"))
      (node (ref "C8") (pin "1") (pinfunction "1_1") (pintype "passive"))
      (node (ref "C9") (pin "1") (pinfunction "1_1") (pintype "passive"))
      (node (ref "CN11") (pin "1") (pinfunction "1_1") (pintype "passive"))
      (node (ref "CN14") (pin "1") (pinfunction "1_1") (pintype "passive"))
      (node (ref "CN15") (pin "4") (pinfunction "VDD_4") (pintype "passive"))
      (node (ref "CN2") (pin "1") (pinfunction "1_1") (pintype "passive"))
      (node (ref "CN3") (pin "1") (pinfunction "1_1") (pintype "passive"))
      (node (ref "CN4") (pin "1") (pinfunction "1_1") (pintype "passive"))
      (node (ref "CN5") (pin "1") (pinfunction "1_1") (pintype "passive"))
      (node (ref "CN7") (pin "2") (pinfunction "2_2") (pintype "passive"))
      (node (ref "CN9") (pin "1") (pinfunction "1_1") (pintype "passive"))
      (node (ref "IC1") (pin "19") (pinfunction "VDD_1_19") (pintype "passive"))
      (node (ref "IC1") (pin "32") (pinfunction "VDD_2_32") (pintype "passive"))
      (node (ref "IC1") (pin "48") (pinfunction "VDDUSB_48") (pintype "passive"))
      (node (ref "IC1") (pin "64") (pinfunction "VDD_3_64") (pintype "passive"))
      (node (ref "L1") (pin "2") (pinfunction "2_2") (pintype "passive"))
      (node (ref "R1") (pin "1") (pinfunction "1_1") (pintype "passive"))
      (node (ref "R10") (pin "2") (pinfunction "2_2") (pintype "passive"))
      (node (ref "R11") (pin "2") (pinfunction "2_2") (pintype "passive"))
      (node (ref "R12") (pin "1") (pinfunction "1_1") (pintype "passive"))
      (node (ref "R13") (pin "2") (pinfunction "2_2") (pintype "passive"))
      (node (ref "R14") (pin "2") (pinfunction "2_2") (pintype "passive"))
      (node (ref "R17") (pin "1") (pinfunction "1_1") (pintype "passive"))
      (node (ref "R18") (pin "1") (pinfunction "1_1") (pintype "passive"))
      (node (ref "R19") (pin "2") (pinfunction "2_2") (pintype "passive"))
      (node (ref "R2") (pin "1") (pinfunction "1_1") (pintype "passive"))
      (node (ref "R20") (pin "2") (pinfunction "2_2") (pintype "passive"))
      (node (ref "R21") (pin "2") (pinfunction "2_2") (pintype "passive"))
      (node (ref "R3") (pin "1") (pinfunction "1_1") (pintype "passive"))
      (node (ref "R4") (pin "1") (pinfunction "1_1") (pintype "passive"))
      (node (ref "R5") (pin "1") (pinfunction "1_1") (pintype "passive"))
      (node (ref "R6") (pin "2") (pinfunction "2_2") (pintype "passive"))
      (node (ref "R7") (pin "2") (pinfunction "2_2") (pintype "passive"))
      (node (ref "R8") (pin "2") (pinfunction "2_2") (pintype "passive"))
      (node (ref "R9") (pin "1") (pinfunction "1_1") (pintype "passive"))
    )
    (net (code "62") (name "VDDA") (class "Default")
      (node (ref "C4") (pin "2") (pinfunction "2_2") (pintype "passive"))
      (node (ref "C5") (pin "2") (pinfunction "2_2") (pintype "passive"))
      (node (ref "C6") (pin "2") (pinfunction "2_2") (pintype "passive"))
      (node (ref "C7") (pin "2") (pinfunction "2_2") (pintype "passive"))
      (node (ref "IC1") (pin "13") (pinfunction "VDDA/VREF+_13") (pintype "passive"))
      (node (ref "L1") (pin "1") (pinfunction "1_1") (pintype "passive"))
    )
    (net (code "63") (name "unconnected-(IC1-PH0-OSC_IN-Pad5)") (class "Default")
      (node (ref "IC1") (pin "5") (pinfunction "PH0-OSC_IN_5") (pintype "passive+no_connect"))
    )
    (net (code "64") (name "unconnected-(IC1-PH1-OSC_OUT-Pad6)") (class "Default")
      (node (ref "IC1") (pin "6") (pinfunction "PH1-OSC_OUT_6") (pintype "passive+no_connect"))
    )
  )
)
